# UART_SBUS_JTAG.net
KiCad netlist of a schematic drawn in Altium Designer
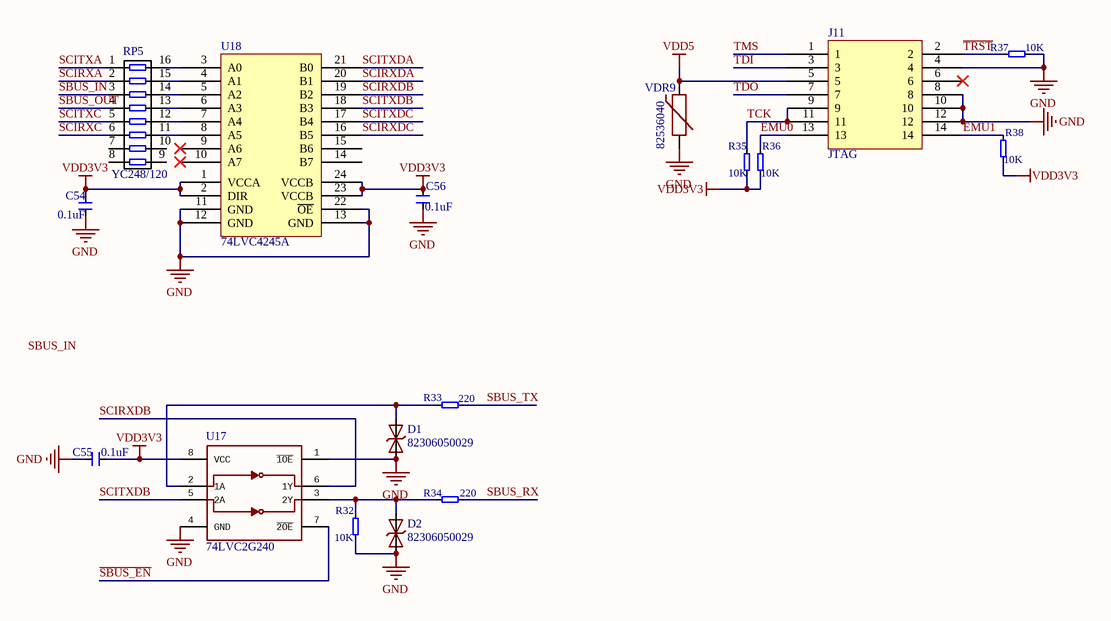
[diagram p0: UART&SBUS&JTAG.SchDoc]

(export (version "E")
  (design (tool "Eeschema 10.0.6"))
  (components
    (comp (ref "C54") (value "0.1uF") (footprint "0603C") (libsource (lib "研发中心原理图库文件") (part "C")))
    (comp (ref "C55") (value "0.1uF") (footprint "0603C") (libsource (lib "研发中心原理图库文件") (part "C")))
    (comp (ref "C56") (value "0.1uF") (footprint "0603C") (libsource (lib "研发中心原理图库文件") (part "C")))
    (comp (ref "D1")
      (value "82306050029")
      (footprint "0603R")
      (libsource (lib "研发中心原理图库文件") (part "DIODE-TVS/Bidirectional"))
    )
    (comp (ref "D2")
      (value "82306050029")
      (footprint "0603R")
      (libsource (lib "研发中心原理图库文件") (part "DIODE-TVS/Bidirectional"))
    )
    (comp (ref "J11") (value "JTAG") (footprint "IDC14") (libsource (lib "研发中心原理图库文件") (part "IDC-14")))
    (comp (ref "R32") (value "10K") (footprint "0603R") (libsource (lib "研发中心原理图库文件") (part "R")))
    (comp (ref "R33") (value "220") (footprint "0603R") (libsource (lib "研发中心原理图库文件") (part "R")))
    (comp (ref "R34") (value "220") (footprint "0603R") (libsource (lib "研发中心原理图库文件") (part "R")))
    (comp (ref "R35") (value "10K") (footprint "0603R") (libsource (lib "研发中心原理图库文件") (part "R")))
    (comp (ref "R36") (value "10K") (footprint "0603R") (libsource (lib "研发中心原理图库文件") (part "R")))
    (comp (ref "R37") (value "10K") (footprint "0603R") (libsource (lib "研发中心原理图库文件") (part "R")))
    (comp (ref "R38") (value "10K") (footprint "0603R") (libsource (lib "研发中心原理图库文件") (part "R")))
    (comp (ref "RP5") (value "YC248/120") (footprint "YC248") (libsource (lib "研发中心原理图库文件") (part "RP")))
    (comp (ref "U17")
      (value "74LVC2G240")
      (footprint "VSSOP-8")
      (libsource (lib "研发中心原理图库文件") (part "74LVC2G240"))
    )
    (comp (ref "U18")
      (value "74LVC4245A")
      (footprint "SSOP24")
      (libsource (lib "研发中心原理图库文件") (part "74LVC4245A"))
    )
    (comp (ref "VDR9")
      (value "82536040")
      (footprint "0603R")
      (libsource (lib "研发中心原理图库文件") (part "Varistor"))
    )
  )
  (nets
    (net (code "1") (name "/EMU0") (class "Default")
      (node (ref "J11") (pin "13") (pinfunction "13_13") (pintype "passive"))
      (node (ref "R36") (pin "2") (pintype "passive"))
    )
    (net (code "2") (name "/EMU1") (class "Default")
      (node (ref "J11") (pin "14") (pinfunction "14_14") (pintype "passive"))
      (node (ref "R38") (pin "2") (pintype "passive"))
    )
    (net (code "3") (name "/SBUS_IN") (class "Default")
      (node (ref "RP5") (pin "3") (pinfunction "3_3") (pintype "passive"))
    )
    (net (code "4") (name "/SBUS_OUT") (class "Default")
      (node (ref "RP5") (pin "4") (pinfunction "4_4") (pintype "passive"))
    )
    (net (code "5") (name "/SBUS_RX") (class "Default") (node (ref "R34") (pin "1") (pintype "passive")))
    (net (code "6") (name "/SBUS_TX") (class "Default") (node (ref "R33") (pin "1") (pintype "passive")))
    (net (code "7") (name "/SCIRXA") (class "Default")
      (node (ref "RP5") (pin "2") (pinfunction "2_2") (pintype "passive"))
    )
    (net (code "8") (name "/SCIRXC") (class "Default")
      (node (ref "RP5") (pin "6") (pinfunction "6_6") (pintype "passive"))
    )
    (net (code "9") (name "/SCIRXDA") (class "Default")
      (node (ref "U18") (pin "20") (pinfunction "B1_20") (pintype "passive"))
    )
    (net (code "10") (name "/SCIRXDB") (class "Default")
      (node (ref "U17") (pin "6") (pinfunction "1Y_6") (pintype "passive"))
      (node (ref "U18") (pin "19") (pinfunction "B2_19") (pintype "passive"))
    )
    (net (code "11") (name "/SCIRXDC") (class "Default")
      (node (ref "U18") (pin "16") (pinfunction "B5_16") (pintype "passive"))
    )
    (net (code "12") (name "/SCITXA") (class "Default")
      (node (ref "RP5") (pin "1") (pinfunction "1_1") (pintype "passive"))
    )
    (net (code "13") (name "/SCITXC") (class "Default")
      (node (ref "RP5") (pin "5") (pinfunction "5_5") (pintype "passive"))
    )
    (net (code "14") (name "/SCITXDA") (class "Default")
      (node (ref "U18") (pin "21") (pinfunction "B0_21") (pintype "passive"))
    )
    (net (code "15") (name "/SCITXDB") (class "Default")
      (node (ref "U17") (pin "5") (pinfunction "2A_5") (pintype "passive"))
      (node (ref "U18") (pin "18") (pinfunction "B3_18") (pintype "passive"))
    )
    (net (code "16") (name "/SCITXDC") (class "Default")
      (node (ref "U18") (pin "17") (pinfunction "B4_17") (pintype "passive"))
    )
    (net (code "17") (name "/TCK") (class "Default")
      (node (ref "J11") (pin "11") (pinfunction "11_11") (pintype "passive"))
      (node (ref "J11") (pin "9") (pinfunction "9_9") (pintype "passive"))
      (node (ref "R35") (pin "2") (pintype "passive"))
    )
    (net (code "18") (name "/TDI") (class "Default")
      (node (ref "J11") (pin "3") (pinfunction "3_3") (pintype "passive"))
    )
    (net (code "19") (name "/TD~{O}") (class "Default")
      (node (ref "J11") (pin "7") (pinfunction "7_7") (pintype "passive"))
    )
    (net (code "20") (name "/TMS") (class "Default")
      (node (ref "J11") (pin "1") (pinfunction "1_1") (pintype "passive"))
    )
    (net (code "21") (name "/~{SBUS_EN}") (class "Default")
      (node (ref "U17") (pin "7") (pinfunction "~{2OE}_7") (pintype "passive"))
    )
    (net (code "22") (name "/~{TRST}") (class "Default")
      (node (ref "J11") (pin "2") (pinfunction "2_2") (pintype "passive"))
      (node (ref "R37") (pin "2") (pintype "passive"))
    )
    (net (code "23") (name "GND") (class "Default")
      (node (ref "C54") (pin "1") (pintype "passive"))
      (node (ref "C55") (pin "2") (pintype "passive"))
      (node (ref "C56") (pin "1") (pintype "passive"))
      (node (ref "D1") (pin "2") (pinfunction "2_2") (pintype "passive"))
      (node (ref "D2") (pin "2") (pinfunction "2_2") (pintype "passive"))
      (node (ref "J11") (pin "10") (pinfunction "10_10") (pintype "passive"))
      (node (ref "J11") (pin "12") (pinfunction "12_12") (pintype "passive"))
      (node (ref "J11") (pin "4") (pinfunction "4_4") (pintype "passive"))
      (node (ref "J11") (pin "8") (pinfunction "8_8") (pintype "passive"))
      (node (ref "R32") (pin "2") (pintype "passive"))
      (node (ref "R37") (pin "1") (pintype "passive"))
      (node (ref "U17") (pin "1") (pinfunction "~{1OE}_1") (pintype "passive"))
      (node (ref "U17") (pin "4") (pinfunction "GND_4") (pintype "open_emitter"))
      (node (ref "U18") (pin "11") (pinfunction "GND_11") (pintype "passive"))
      (node (ref "U18") (pin "12") (pinfunction "GND_12") (pintype "passive"))
      (node (ref "U18") (pin "13") (pinfunction "GND_13") (pintype "passive"))
      (node (ref "U18") (pin "22") (pinfunction "~{OE}_22") (pintype "passive"))
      (node (ref "VDR9") (pin "1") (pinfunction "1_1") (pintype "passive"))
    )
    (net (code "24") (name "Net-(U17-1A)") (class "Default")
      (node (ref "D1") (pin "1") (pinfunction "1_1") (pintype "passive"))
      (node (ref "R33") (pin "2") (pintype "passive"))
      (node (ref "U17") (pin "2") (pinfunction "1A_2") (pintype "passive"))
    )
    (net (code "25") (name "Net-(U17-2Y)") (class "Default")
      (node (ref "D2") (pin "1") (pinfunction "1_1") (pintype "passive"))
      (node (ref "R32") (pin "1") (pintype "passive"))
      (node (ref "R34") (pin "2") (pintype "passive"))
      (node (ref "U17") (pin "3") (pinfunction "2Y_3") (pintype "passive"))
    )
    (net (code "26") (name "Net-(U18-A0)") (class "Default")
      (node (ref "RP5") (pin "16") (pinfunction "16_16") (pintype "passive"))
      (node (ref "U18") (pin "3") (pinfunction "A0_3") (pintype "passive"))
    )
    (net (code "27") (name "Net-(U18-A1)") (class "Default")
      (node (ref "RP5") (pin "15") (pinfunction "15_15") (pintype "passive"))
      (node (ref "U18") (pin "4") (pinfunction "A1_4") (pintype "passive"))
    )
    (net (code "28") (name "Net-(U18-A2)") (class "Default")
      (node (ref "RP5") (pin "14") (pinfunction "14_14") (pintype "passive"))
      (node (ref "U18") (pin "5") (pinfunction "A2_5") (pintype "passive"))
    )
    (net (code "29") (name "Net-(U18-A3)") (class "Default")
      (node (ref "RP5") (pin "13") (pinfunction "13_13") (pintype "passive"))
      (node (ref "U18") (pin "6") (pinfunction "A3_6") (pintype "passive"))
    )
    (net (code "30") (name "Net-(U18-A4)") (class "Default")
      (node (ref "RP5") (pin "12") (pinfunction "12_12") (pintype "passive"))
      (node (ref "U18") (pin "7") (pinfunction "A4_7") (pintype "passive"))
    )
    (net (code "31") (name "Net-(U18-A5)") (class "Default")
      (node (ref "RP5") (pin "11") (pinfunction "11_11") (pintype "passive"))
      (node (ref "U18") (pin "8") (pinfunction "A5_8") (pintype "passive"))
    )
    (net (code "32") (name "VDD3V3") (class "Default")
      (node (ref "C54") (pin "2") (pintype "passive"))
      (node (ref "C55") (pin "1") (pintype "passive"))
      (node (ref "C56") (pin "2") (pintype "passive"))
      (node (ref "R35") (pin "1") (pintype "passive"))
      (node (ref "R36") (pin "1") (pintype "passive"))
      (node (ref "R38") (pin "1") (pintype "passive"))
      (node (ref "U17") (pin "8") (pinfunction "VCC_8") (pintype "open_emitter"))
      (node (ref "U18") (pin "1") (pinfunction "VCCA_1") (pintype "passive"))
      (node (ref "U18") (pin "2") (pinfunction "DIR_2") (pintype "passive"))
      (node (ref "U18") (pin "23") (pinfunction "VCCB_23") (pintype "passive"))
      (node (ref "U18") (pin "24") (pinfunction "VCCB_24") (pintype "passive"))
    )
    (net (code "33") (name "VDD5") (class "Default")
      (node (ref "J11") (pin "5") (pinfunction "5_5") (pintype "passive"))
      (node (ref "VDR9") (pin "2") (pinfunction "2_2") (pintype "passive"))
    )
    (net (code "34") (name "unconnected-(J11-Pad6)") (class "Default")
      (node (ref "J11") (pin "6") (pinfunction "6_6") (pintype "passive+no_connect"))
    )
    (net (code "35") (name "unconnected-(RP5-Pad7)") (class "Default")
      (node (ref "RP5") (pin "7") (pinfunction "7_7") (pintype "passive"))
    )
    (net (code "36") (name "unconnected-(RP5-Pad8)") (class "Default")
      (node (ref "RP5") (pin "8") (pinfunction "8_8") (pintype "passive"))
    )
    (net (code "37") (name "unconnected-(RP5-Pad9)") (class "Default")
      (node (ref "RP5") (pin "9") (pinfunction "9_9") (pintype "passive"))
    )
    (net (code "38") (name "unconnected-(RP5-Pad10)") (class "Default")
      (node (ref "RP5") (pin "10") (pinfunction "10_10") (pintype "passive"))
    )
    (net (code "39") (name "unconnected-(U18-A6-Pad9)") (class "Default")
      (node (ref "U18") (pin "9") (pinfunction "A6_9") (pintype "passive+no_connect"))
    )
    (net (code "40") (name "unconnected-(U18-A7-Pad10)") (class "Default")
      (node (ref "U18") (pin "10") (pinfunction "A7_10") (pintype "passive+no_connect"))
    )
    (net (code "41") (name "unconnected-(U18-B6-Pad15)") (class "Default")
      (node (ref "U18") (pin "15") (pinfunction "B6_15") (pintype "passive"))
    )
    (net (code "42") (name "unconnected-(U18-B7-Pad14)") (class "Default")
      (node (ref "U18") (pin "14") (pinfunction "B7_14") (pintype "passive"))
    )
  )
)
